# FSKmodem.net
KiCad netlist of a schematic drawn in EAGLE
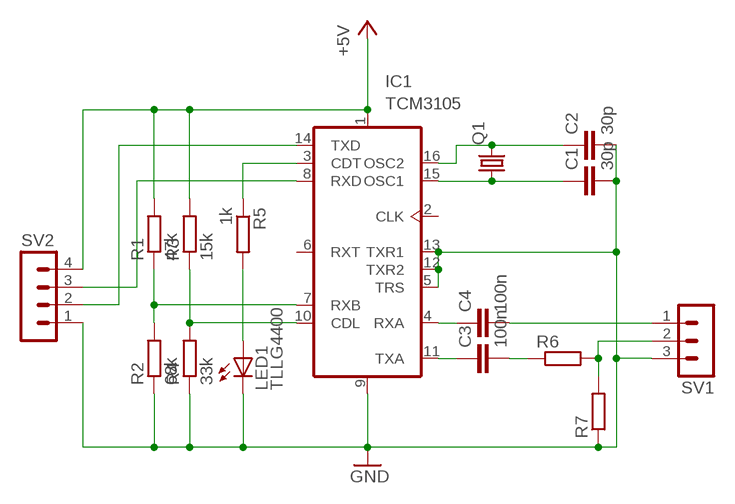
[diagram p0: schematic, sheet 1]

(export (version "E")
  (design (tool "Eeschema 10.0.6"))
  (components
    (comp (ref "C1")
      (value "30p")
      (footprint "eagle-import:C025-024X044")
      (libsource (lib "eagle-import") (part "C-EU025-024X044"))
    )
    (comp (ref "C2")
      (value "30p")
      (footprint "eagle-import:C025-024X044")
      (libsource (lib "eagle-import") (part "C-EU025-024X044"))
    )
    (comp (ref "C3")
      (value "100n")
      (footprint "eagle-import:C025-024X044")
      (libsource (lib "eagle-import") (part "C-EU025-024X044"))
    )
    (comp (ref "C4")
      (value "100n")
      (footprint "eagle-import:C025-024X044")
      (libsource (lib "eagle-import") (part "C-EU025-024X044"))
    )
    (comp (ref "IC1")
      (value "TCM3105")
      (footprint "eagle-import:DIL16")
      (libsource (lib "eagle-import") (part "TCM3105"))
    )
    (comp (ref "LED1")
      (value "TLLG4400")
      (footprint "eagle-import:LED3MM")
      (fields (field (name "MF") "VISHAY SEMICONDUCTOR"))
      (libsource (lib "eagle-import") (part "TLLG4400"))
    )
    (comp (ref "Q1")
      (value "CRYSTALHC49U70")
      (footprint "eagle-import:HC49U70")
      (libsource (lib "eagle-import") (part "CRYSTALHC49U70"))
    )
    (comp (ref "R1")
      (value "47k")
      (footprint "eagle-import:0204_5")
      (libsource (lib "eagle-import") (part "R-EU_0204/5"))
    )
    (comp (ref "R2")
      (value "68k")
      (footprint "eagle-import:0204_5")
      (libsource (lib "eagle-import") (part "R-EU_0204/5"))
    )
    (comp (ref "R3")
      (value "15k")
      (footprint "eagle-import:0204_5")
      (libsource (lib "eagle-import") (part "R-EU_0204/5"))
    )
    (comp (ref "R4")
      (value "33k")
      (footprint "eagle-import:0204_5")
      (libsource (lib "eagle-import") (part "R-EU_0204/5"))
    )
    (comp (ref "R5")
      (value "1k")
      (footprint "eagle-import:0204_5")
      (libsource (lib "eagle-import") (part "R-EU_0204/5"))
    )
    (comp (ref "R6")
      (value "R-EU_0204/5")
      (footprint "eagle-import:0204_5")
      (libsource (lib "eagle-import") (part "R-EU_0204/5"))
    )
    (comp (ref "R7")
      (value "R-EU_0204/5")
      (footprint "eagle-import:0204_5")
      (libsource (lib "eagle-import") (part "R-EU_0204/5"))
    )
    (comp (ref "SV1")
      (value "MA03-1")
      (footprint "eagle-import:MA03-1")
      (libsource (lib "eagle-import") (part "MA03-1"))
    )
    (comp (ref "SV2")
      (value "MA04-1")
      (footprint "eagle-import:MA04-1")
      (libsource (lib "eagle-import") (part "MA04-1"))
    )
  )
  (nets
    (net (code "1") (name "+5V") (class "Default")
      (node (ref "IC1") (pin "1") (pinfunction "VDD_1") (pintype "power_in"))
      (node (ref "R1") (pin "2") (pinfunction "2_2") (pintype "passive"))
      (node (ref "R3") (pin "2") (pinfunction "2_2") (pintype "passive"))
      (node (ref "SV2") (pin "4") (pinfunction "4_4") (pintype "passive"))
    )
    (net (code "2") (name "GND") (class "Default")
      (node (ref "C1") (pin "2") (pinfunction "2_2") (pintype "passive"))
      (node (ref "C2") (pin "2") (pinfunction "2_2") (pintype "passive"))
      (node (ref "IC1") (pin "12") (pinfunction "TXR2_12") (pintype "input"))
      (node (ref "IC1") (pin "13") (pinfunction "TXR1_13") (pintype "input"))
      (node (ref "IC1") (pin "5") (pinfunction "TRS_5") (pintype "input"))
      (node (ref "IC1") (pin "9") (pinfunction "VSS_9") (pintype "power_in"))
      (node (ref "LED1") (pin "K") (pinfunction "C_K") (pintype "passive"))
      (node (ref "R2") (pin "1") (pinfunction "1_1") (pintype "passive"))
      (node (ref "R4") (pin "1") (pinfunction "1_1") (pintype "passive"))
      (node (ref "R7") (pin "1") (pinfunction "1_1") (pintype "passive"))
      (node (ref "SV1") (pin "3") (pinfunction "3_3") (pintype "passive"))
      (node (ref "SV2") (pin "1") (pinfunction "1_1") (pintype "passive"))
    )
    (net (code "3") (name "Net-(C3-Pad2)") (class "Default")
      (node (ref "C3") (pin "2") (pinfunction "2_2") (pintype "passive"))
      (node (ref "R6") (pin "1") (pinfunction "1_1") (pintype "passive"))
    )
    (net (code "4") (name "Net-(C4-Pad2)") (class "Default")
      (node (ref "C4") (pin "2") (pinfunction "2_2") (pintype "passive"))
      (node (ref "SV1") (pin "1") (pinfunction "1_1") (pintype "passive"))
    )
    (net (code "5") (name "Net-(IC1-CDL)") (class "Default")
      (node (ref "IC1") (pin "10") (pinfunction "CDL_10") (pintype "bidirectional"))
      (node (ref "R3") (pin "1") (pinfunction "1_1") (pintype "passive"))
      (node (ref "R4") (pin "2") (pinfunction "2_2") (pintype "passive"))
    )
    (net (code "6") (name "Net-(IC1-CDT)") (class "Default")
      (node (ref "IC1") (pin "3") (pinfunction "CDT_3") (pintype "output"))
      (node (ref "R5") (pin "1") (pinfunction "1_1") (pintype "passive"))
    )
    (net (code "7") (name "Net-(IC1-OSC1)") (class "Default")
      (node (ref "C1") (pin "1") (pinfunction "1_1") (pintype "passive"))
      (node (ref "IC1") (pin "15") (pinfunction "OSC1_15") (pintype "bidirectional"))
      (node (ref "Q1") (pin "1") (pinfunction "1_1") (pintype "passive"))
    )
    (net (code "8") (name "Net-(IC1-OSC2)") (class "Default")
      (node (ref "C2") (pin "1") (pinfunction "1_1") (pintype "passive"))
      (node (ref "IC1") (pin "16") (pinfunction "OSC2_16") (pintype "bidirectional"))
      (node (ref "Q1") (pin "2") (pinfunction "2_2") (pintype "passive"))
    )
    (net (code "9") (name "Net-(IC1-RXA)") (class "Default")
      (node (ref "C4") (pin "1") (pinfunction "1_1") (pintype "passive"))
      (node (ref "IC1") (pin "4") (pinfunction "RXA_4") (pintype "input"))
    )
    (net (code "10") (name "Net-(IC1-RXB)") (class "Default")
      (node (ref "IC1") (pin "7") (pinfunction "RXB_7") (pintype "bidirectional"))
      (node (ref "R1") (pin "1") (pinfunction "1_1") (pintype "passive"))
      (node (ref "R2") (pin "2") (pinfunction "2_2") (pintype "passive"))
    )
    (net (code "11") (name "Net-(IC1-RXD)") (class "Default")
      (node (ref "IC1") (pin "8") (pinfunction "RXD_8") (pintype "output"))
      (node (ref "SV2") (pin "3") (pinfunction "3_3") (pintype "passive"))
    )
    (net (code "12") (name "Net-(IC1-TXA)") (class "Default")
      (node (ref "C3") (pin "1") (pinfunction "1_1") (pintype "passive"))
      (node (ref "IC1") (pin "11") (pinfunction "TXA_11") (pintype "output"))
    )
    (net (code "13") (name "Net-(IC1-TXD)") (class "Default")
      (node (ref "IC1") (pin "14") (pinfunction "TXD_14") (pintype "input"))
      (node (ref "SV2") (pin "2") (pinfunction "2_2") (pintype "passive"))
    )
    (net (code "14") (name "Net-(LED1-PadA)") (class "Default")
      (node (ref "LED1") (pin "A") (pinfunction "A_A") (pintype "passive"))
      (node (ref "R5") (pin "2") (pinfunction "2_2") (pintype "passive"))
    )
    (net (code "15") (name "Net-(R6-Pad2)") (class "Default")
      (node (ref "R6") (pin "2") (pinfunction "2_2") (pintype "passive"))
      (node (ref "R7") (pin "2") (pinfunction "2_2") (pintype "passive"))
      (node (ref "SV1") (pin "2") (pinfunction "2_2") (pintype "passive"))
    )
    (net (code "16") (name "unconnected-(IC1-CLK-Pad2)") (class "Default")
      (node (ref "IC1") (pin "2") (pinfunction "CLK_2") (pintype "output"))
    )
    (net (code "17") (name "unconnected-(IC1-RXT-Pad6)") (class "Default")
      (node (ref "IC1") (pin "6") (pinfunction "RXT_6") (pintype "bidirectional"))
    )
  )
)
